# GanglionCarrierBoard.net
KiCad netlist of a schematic drawn in EAGLE
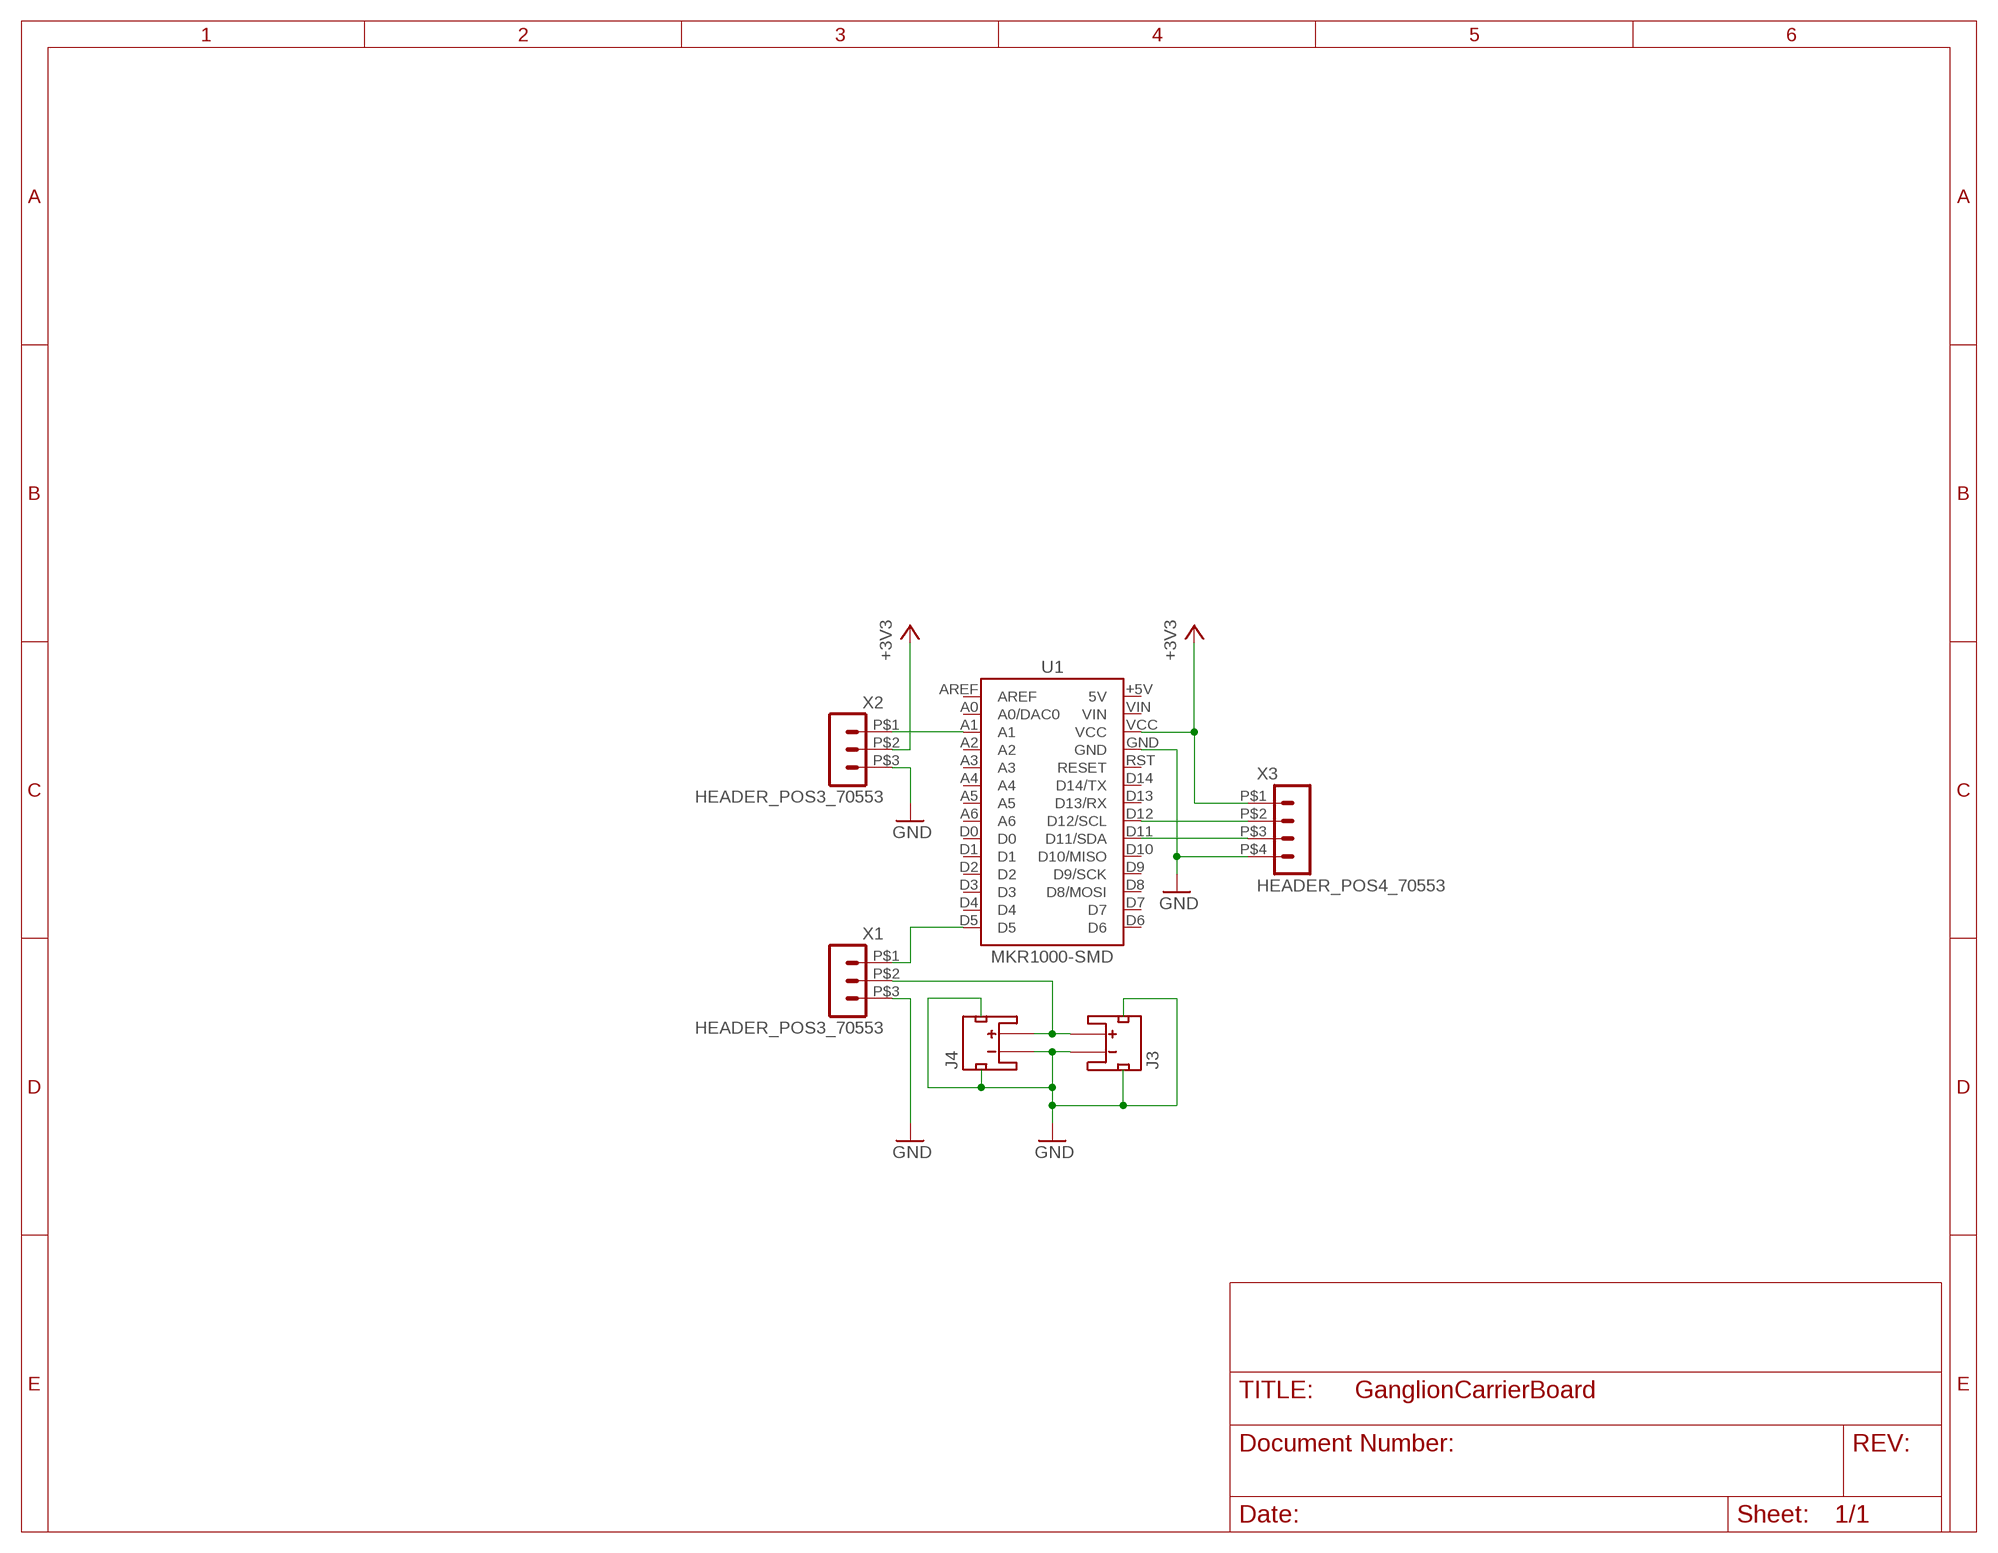
[diagram p0: schematic, sheet 1]

(export (version "E")
  (design (tool "Eeschema 10.0.6"))
  (components
    (comp (ref "J3")
      (value "JST_2MM_MALE")
      (footprint "eagle-import:JST-2-SMD")
      (libsource (lib "eagle-import") (part "JST_2MM_MALE"))
    )
    (comp (ref "J4")
      (value "JST_2MM_MALE")
      (footprint "eagle-import:JST-2-SMD")
      (libsource (lib "eagle-import") (part "JST_2MM_MALE"))
    )
    (comp (ref "U1")
      (value "MKR1000-SMD")
      (footprint "eagle-import:MKR1000-SMD")
      (libsource (lib "eagle-import") (part "MKR1000-SMD"))
    )
    (comp (ref "X1")
      (value "HEADER_POS3_70553")
      (footprint "eagle-import:70553-POS3")
      (libsource (lib "eagle-import") (part "HEADER_POS3_?70553"))
    )
    (comp (ref "X2")
      (value "HEADER_POS3_70553")
      (footprint "eagle-import:70553-POS3")
      (libsource (lib "eagle-import") (part "HEADER_POS3_?70553"))
    )
    (comp (ref "X3")
      (value "HEADER_POS4_70553")
      (footprint "eagle-import:70553-POS4")
      (libsource (lib "eagle-import") (part "HEADER_POS4_?70553"))
    )
  )
  (nets
    (net (code "1") (name "+3V3") (class "Default")
      (node (ref "U1") (pin "VCC") (pinfunction "VCC_VCC") (pintype "bidirectional"))
      (node (ref "X2") (pin "P$2") (pinfunction "2_P$2") (pintype "passive"))
      (node (ref "X3") (pin "P$1") (pinfunction "1_P$1") (pintype "passive"))
    )
    (net (code "2") (name "GND") (class "Default")
      (node (ref "J3") (pin "1") (pinfunction "-_1") (pintype "bidirectional"))
      (node (ref "J3") (pin "NC1") (pinfunction "PAD1_NC1") (pintype "bidirectional"))
      (node (ref "J3") (pin "NC2") (pinfunction "PAD2_NC2") (pintype "bidirectional"))
      (node (ref "J4") (pin "1") (pinfunction "-_1") (pintype "bidirectional"))
      (node (ref "J4") (pin "NC1") (pinfunction "PAD1_NC1") (pintype "bidirectional"))
      (node (ref "J4") (pin "NC2") (pinfunction "PAD2_NC2") (pintype "bidirectional"))
      (node (ref "U1") (pin "GND") (pinfunction "GND_GND") (pintype "bidirectional"))
      (node (ref "X1") (pin "P$3") (pinfunction "3_P$3") (pintype "passive"))
      (node (ref "X2") (pin "P$3") (pinfunction "3_P$3") (pintype "passive"))
      (node (ref "X3") (pin "P$4") (pinfunction "4_P$4") (pintype "passive"))
    )
    (net (code "3") (name "Net-(J3-+)") (class "Default")
      (node (ref "J3") (pin "2") (pinfunction "+_2") (pintype "bidirectional"))
      (node (ref "J4") (pin "2") (pinfunction "+_2") (pintype "bidirectional"))
      (node (ref "X1") (pin "P$2") (pinfunction "2_P$2") (pintype "passive"))
    )
    (net (code "4") (name "Net-(U1-D11{slash}SDA)") (class "Default")
      (node (ref "U1") (pin "D11") (pinfunction "D11/SDA_D11") (pintype "bidirectional"))
      (node (ref "X3") (pin "P$3") (pinfunction "3_P$3") (pintype "passive"))
    )
    (net (code "5") (name "Net-(U1-D12{slash}SCL)") (class "Default")
      (node (ref "U1") (pin "D12") (pinfunction "D12/SCL_D12") (pintype "bidirectional"))
      (node (ref "X3") (pin "P$2") (pinfunction "2_P$2") (pintype "passive"))
    )
    (net (code "6") (name "Net-(X1-1)") (class "Default")
      (node (ref "U1") (pin "D5") (pinfunction "D5_D5") (pintype "bidirectional"))
      (node (ref "X1") (pin "P$1") (pinfunction "1_P$1") (pintype "passive"))
    )
    (net (code "7") (name "Net-(X2-1)") (class "Default")
      (node (ref "U1") (pin "A1") (pinfunction "A1_A1") (pintype "bidirectional"))
      (node (ref "X2") (pin "P$1") (pinfunction "1_P$1") (pintype "passive"))
    )
    (net (code "8") (name "unconnected-(U1-5V-Pad+5V)") (class "Default")
      (node (ref "U1") (pin "+5V") (pinfunction "5V_+5V") (pintype "bidirectional"))
    )
    (net (code "9") (name "unconnected-(U1-A0{slash}DAC0-PadA0)") (class "Default")
      (node (ref "U1") (pin "A0") (pinfunction "A0/DAC0_A0") (pintype "bidirectional"))
    )
    (net (code "10") (name "unconnected-(U1-D8{slash}MOSI-PadD8)") (class "Default")
      (node (ref "U1") (pin "D8") (pinfunction "D8/MOSI_D8") (pintype "bidirectional"))
    )
    (net (code "11") (name "unconnected-(U1-D9{slash}SCK-PadD9)") (class "Default")
      (node (ref "U1") (pin "D9") (pinfunction "D9/SCK_D9") (pintype "bidirectional"))
    )
    (net (code "12") (name "unconnected-(U1-D10{slash}MISO-PadD10)") (class "Default")
      (node (ref "U1") (pin "D10") (pinfunction "D10/MISO_D10") (pintype "bidirectional"))
    )
    (net (code "13") (name "unconnected-(U1-D13{slash}RX-PadD13)") (class "Default")
      (node (ref "U1") (pin "D13") (pinfunction "D13/RX_D13") (pintype "bidirectional"))
    )
    (net (code "14") (name "unconnected-(U1-D14{slash}TX-PadD14)") (class "Default")
      (node (ref "U1") (pin "D14") (pinfunction "D14/TX_D14") (pintype "bidirectional"))
    )
    (net (code "15") (name "unconnected-(U1-PadA2)") (class "Default")
      (node (ref "U1") (pin "A2") (pinfunction "A2_A2") (pintype "bidirectional"))
    )
    (net (code "16") (name "unconnected-(U1-PadA3)") (class "Default")
      (node (ref "U1") (pin "A3") (pinfunction "A3_A3") (pintype "bidirectional"))
    )
    (net (code "17") (name "unconnected-(U1-PadA4)") (class "Default")
      (node (ref "U1") (pin "A4") (pinfunction "A4_A4") (pintype "bidirectional"))
    )
    (net (code "18") (name "unconnected-(U1-PadA5)") (class "Default")
      (node (ref "U1") (pin "A5") (pinfunction "A5_A5") (pintype "bidirectional"))
    )
    (net (code "19") (name "unconnected-(U1-PadA6)") (class "Default")
      (node (ref "U1") (pin "A6") (pinfunction "A6_A6") (pintype "bidirectional"))
    )
    (net (code "20") (name "unconnected-(U1-PadAREF)") (class "Default")
      (node (ref "U1") (pin "AREF") (pinfunction "AREF_AREF") (pintype "bidirectional"))
    )
    (net (code "21") (name "unconnected-(U1-PadD0)") (class "Default")
      (node (ref "U1") (pin "D0") (pinfunction "D0_D0") (pintype "bidirectional"))
    )
    (net (code "22") (name "unconnected-(U1-PadD1)") (class "Default")
      (node (ref "U1") (pin "D1") (pinfunction "D1_D1") (pintype "bidirectional"))
    )
    (net (code "23") (name "unconnected-(U1-PadD2)") (class "Default")
      (node (ref "U1") (pin "D2") (pinfunction "D2_D2") (pintype "bidirectional"))
    )
    (net (code "24") (name "unconnected-(U1-PadD3)") (class "Default")
      (node (ref "U1") (pin "D3") (pinfunction "D3_D3") (pintype "bidirectional"))
    )
    (net (code "25") (name "unconnected-(U1-PadD4)") (class "Default")
      (node (ref "U1") (pin "D4") (pinfunction "D4_D4") (pintype "bidirectional"))
    )
    (net (code "26") (name "unconnected-(U1-PadD6)") (class "Default")
      (node (ref "U1") (pin "D6") (pinfunction "D6_D6") (pintype "bidirectional"))
    )
    (net (code "27") (name "unconnected-(U1-PadD7)") (class "Default")
      (node (ref "U1") (pin "D7") (pinfunction "D7_D7") (pintype "bidirectional"))
    )
    (net (code "28") (name "unconnected-(U1-PadVIN)") (class "Default")
      (node (ref "U1") (pin "VIN") (pinfunction "VIN_VIN") (pintype "bidirectional"))
    )
    (net (code "29") (name "unconnected-(U1-RESET-PadRST)") (class "Default")
      (node (ref "U1") (pin "RST") (pinfunction "RESET_RST") (pintype "bidirectional"))
    )
  )
)
